# m3406.net
KiCad netlist of a schematic drawn in Altium Designer
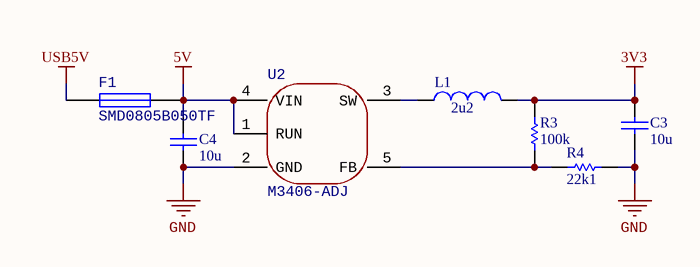
[diagram p0: m3406.SchDoc]

(export (version "E")
  (design (tool "Eeschema 10.0.6"))
  (components
    (comp (ref "C3")
      (value "10u")
      (footprint "footprints:CAPC160X80X90L30N")
      (fields
        (field (name "MPN") "TCC0603X5R106K100CT")
        (field (name "MANUFACTURER") "CCTC(三环)")
        (field (name "Comment") "Capacitor")
      )
      (libsource (lib "std_lib") (part "Capacitor"))
    )
    (comp (ref "C4")
      (value "10u")
      (footprint "footprints:CAPC160X80X90L30N")
      (fields
        (field (name "MPN") "TCC0603X5R106K100CT")
        (field (name "MANUFACTURER") "CCTC(三环)")
        (field (name "Comment") "Capacitor")
      )
      (libsource (lib "std_lib") (part "Capacitor"))
    )
    (comp (ref "F1")
      (value "SMD0805B050TF")
      (footprint "footprints:FUSC210X135X125L37N")
      (description "Fuse")
      (libsource (lib "Miscellaneous Devices") (part "Fuse 1"))
    )
    (comp (ref "L1")
      (value "2u2")
      (footprint "footprints:INDC200X160X105L60N")
      (fields
        (field (name "MPN") "SFE201610-2R2M")
        (field (name "MANUFACTURER") "DDY(德立)")
        (field (name "Comment") "Inductor")
      )
      (libsource (lib "std_lib") (part "Inductor"))
    )
    (comp (ref "R3")
      (value "100k")
      (footprint "footprints:RESC100X50X35L25N")
      (fields
        (field (name "MPN") "RTT021003FTH")
        (field (name "MANUFACTURER") "RALEC(旺诠)")
        (field (name "Comment") "Resistor")
      )
      (libsource (lib "std_lib") (part "Resistor"))
    )
    (comp (ref "R4")
      (value "22k1")
      (footprint "footprints:RESC100X50X35L25N")
      (fields
        (field (name "MPN") "RTT022212FTH")
        (field (name "MANUFACTURER") "RALEC(旺诠)")
        (field (name "Comment") "Resistor")
      )
      (libsource (lib "std_lib") (part "Resistor"))
    )
    (comp (ref "U2")
      (value "M3406-ADJ")
      (footprint "footprints:SOT23-5P95_280X110L37X40N")
      (description "Vin=2V~6V,800mA,DCDC")
      (fields (field (name "MANUFACTURER") "西安航天民芯"))
      (libsource (lib "Sch") (part "M3406-ADJ"))
    )
  )
  (nets
    (net (code "1") (name "3V3") (class "Default")
      (node (ref "C3") (pin "2") (pinfunction "2_2") (pintype "passive"))
      (node (ref "L1") (pin "2") (pinfunction "2_2") (pintype "passive"))
      (node (ref "R3") (pin "2") (pinfunction "2_2") (pintype "passive"))
    )
    (net (code "2") (name "5V") (class "Default")
      (node (ref "C4") (pin "2") (pinfunction "2_2") (pintype "passive"))
      (node (ref "F1") (pin "2") (pinfunction "2_2") (pintype "passive"))
      (node (ref "U2") (pin "1") (pinfunction "RUN_1") (pintype "passive"))
      (node (ref "U2") (pin "4") (pinfunction "VIN_4") (pintype "passive"))
    )
    (net (code "3") (name "GND") (class "Default")
      (node (ref "C3") (pin "1") (pinfunction "1_1") (pintype "passive"))
      (node (ref "C4") (pin "1") (pinfunction "1_1") (pintype "passive"))
      (node (ref "R4") (pin "1") (pinfunction "1_1") (pintype "passive"))
      (node (ref "U2") (pin "2") (pinfunction "GND_2") (pintype "passive"))
    )
    (net (code "4") (name "Net-(U2-FB)") (class "Default")
      (node (ref "R3") (pin "1") (pinfunction "1_1") (pintype "passive"))
      (node (ref "R4") (pin "2") (pinfunction "2_2") (pintype "passive"))
      (node (ref "U2") (pin "5") (pinfunction "FB_5") (pintype "passive"))
    )
    (net (code "5") (name "Net-(U2-SW)") (class "Default")
      (node (ref "L1") (pin "1") (pinfunction "1_1") (pintype "passive"))
      (node (ref "U2") (pin "3") (pinfunction "SW_3") (pintype "passive"))
    )
    (net (code "6") (name "USB5V") (class "Default")
      (node (ref "F1") (pin "1") (pinfunction "1_1") (pintype "passive"))
    )
  )
)
